# DDS_Sine_Sweeper.net
KiCad netlist of a schematic drawn in EAGLE
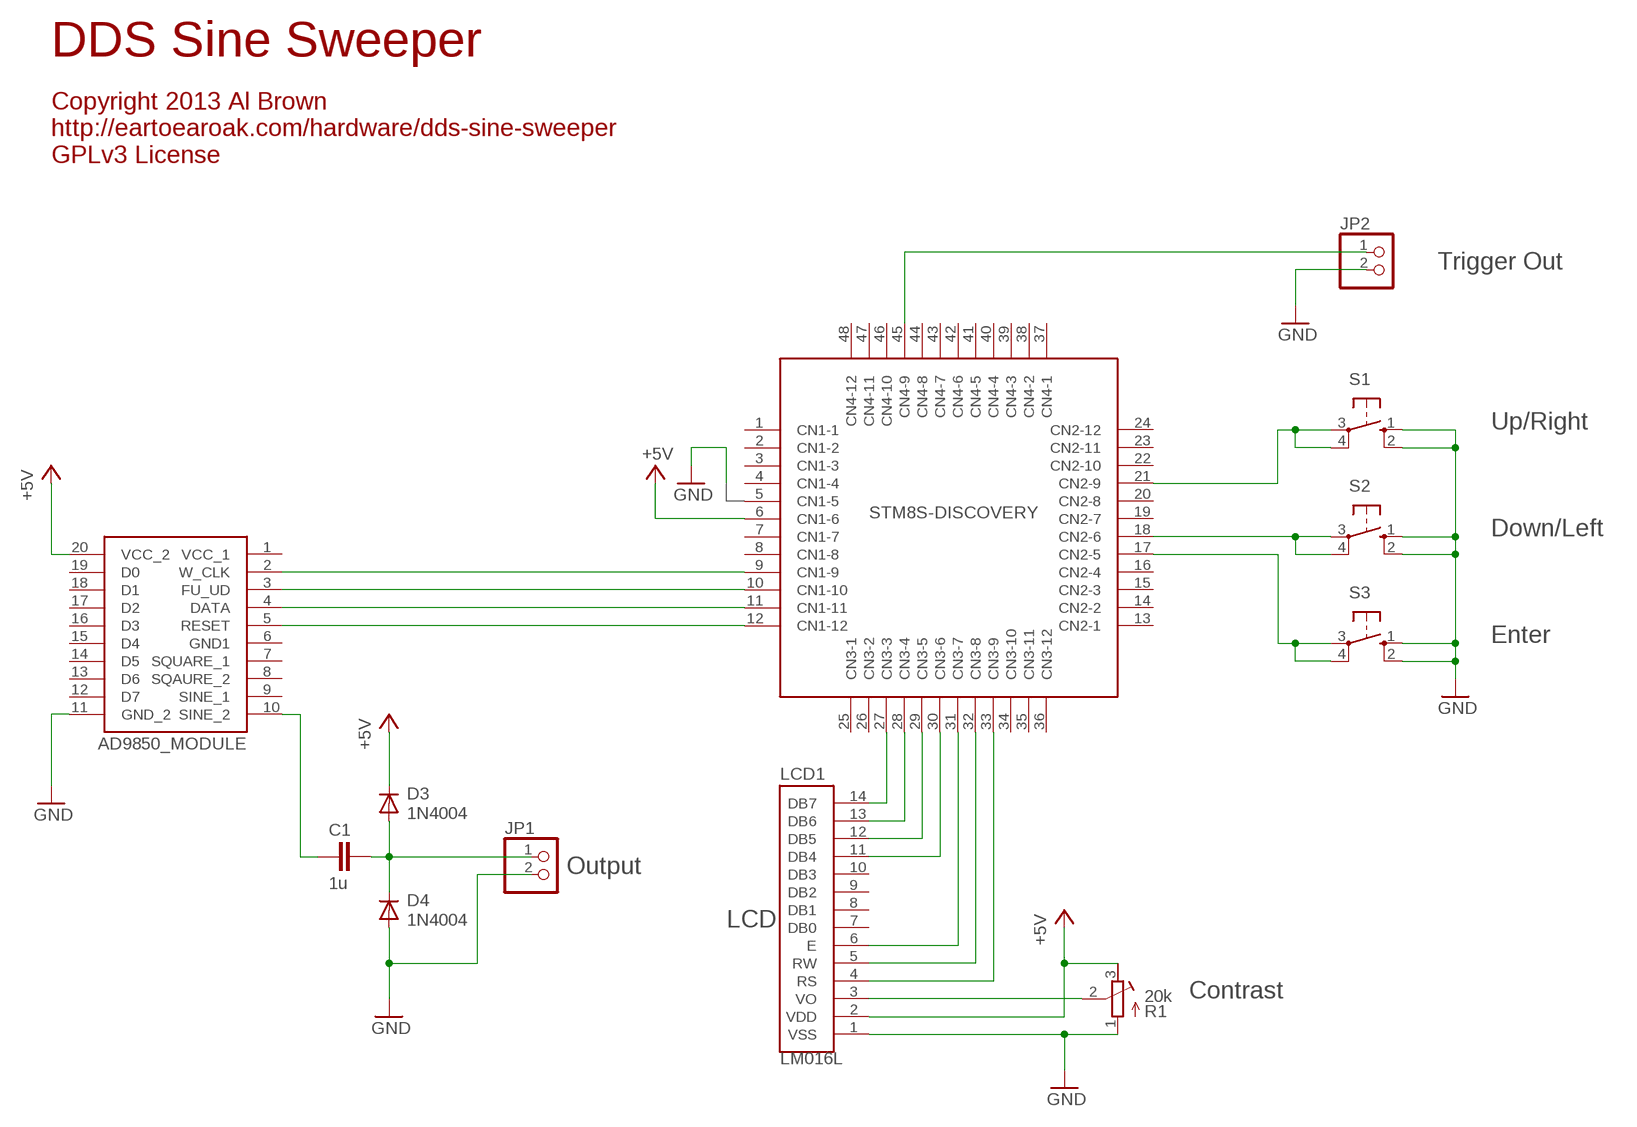
[diagram p0: schematic, sheet 1]

(export (version "E")
  (design (tool "Eeschema 10.0.6"))
  (components
    (comp (ref "BOARD1")
      (value "STM8S-DISCOVERY")
      (footprint "eagle-import:STM8S-DISCOVERY")
      (libsource (lib "eagle-import") (part "STM8S-DISCOVERY"))
    )
    (comp (ref "BOARD2")
      (value "AD9850_MODULE")
      (footprint "eagle-import:10X2")
      (libsource (lib "eagle-import") (part "AD9850_MODULE"))
    )
    (comp (ref "C1")
      (value "1u")
      (footprint "eagle-import:C025_050-024X070")
      (libsource (lib "eagle-import") (part "C-EUC025_050-024X070"))
    )
    (comp (ref "D3")
      (value "1N4004")
      (footprint "eagle-import:DO41-10")
      (libsource (lib "eagle-import") (part "1N4004"))
    )
    (comp (ref "D4")
      (value "1N4004")
      (footprint "eagle-import:DO41-10")
      (libsource (lib "eagle-import") (part "1N4004"))
    )
    (comp (ref "JP1")
      (value "PINHD-1X2")
      (footprint "eagle-import:1X02")
      (libsource (lib "eagle-import") (part "PINHD-1X2"))
    )
    (comp (ref "JP2")
      (value "PINHD-1X2")
      (footprint "eagle-import:1X02")
      (libsource (lib "eagle-import") (part "PINHD-1X2"))
    )
    (comp (ref "LCD1")
      (value "LM016L")
      (footprint "eagle-import:LM016L")
      (libsource (lib "eagle-import") (part "LM016L"))
    )
    (comp (ref "R1")
      (value "20k")
      (footprint "eagle-import:RTRIM3339P")
      (libsource (lib "eagle-import") (part "R-TRIMM3339P"))
    )
    (comp (ref "S1")
      (value "10-XX")
      (footprint "eagle-import:B3F-10XX")
      (fields (field (name "MPN") "B3F-1000"))
      (libsource (lib "eagle-import") (part "10-XX"))
    )
    (comp (ref "S2")
      (value "10-XX")
      (footprint "eagle-import:B3F-10XX")
      (fields (field (name "MPN") "B3F-1000"))
      (libsource (lib "eagle-import") (part "10-XX"))
    )
    (comp (ref "S3")
      (value "10-XX")
      (footprint "eagle-import:B3F-10XX")
      (fields (field (name "MPN") "B3F-1000"))
      (libsource (lib "eagle-import") (part "10-XX"))
    )
  )
  (nets
    (net (code "1") (name "+5V") (class "Default")
      (node (ref "BOARD1") (pin "6") (pinfunction "CN1-6_6") (pintype "bidirectional"))
      (node (ref "BOARD2") (pin "20") (pinfunction "VCC_2_20") (pintype "bidirectional"))
      (node (ref "D3") (pin "C") (pinfunction "C_C") (pintype "passive"))
      (node (ref "LCD1") (pin "2") (pinfunction "VDD_2") (pintype "bidirectional"))
      (node (ref "R1") (pin "3") (pinfunction "A_3") (pintype "passive"))
    )
    (net (code "2") (name "GND") (class "Default")
      (node (ref "BOARD2") (pin "11") (pinfunction "GND_2_11") (pintype "bidirectional"))
      (node (ref "D4") (pin "A") (pinfunction "A_A") (pintype "passive"))
      (node (ref "JP1") (pin "2") (pinfunction "2_2") (pintype "passive"))
      (node (ref "JP2") (pin "2") (pinfunction "2_2") (pintype "passive"))
      (node (ref "LCD1") (pin "1") (pinfunction "VSS_1") (pintype "bidirectional"))
      (node (ref "R1") (pin "1") (pinfunction "E_1") (pintype "passive"))
      (node (ref "S1") (pin "1") (pinfunction "S_1") (pintype "passive"))
      (node (ref "S1") (pin "2") (pinfunction "S1_2") (pintype "passive"))
      (node (ref "S2") (pin "1") (pinfunction "S_1") (pintype "passive"))
      (node (ref "S2") (pin "2") (pinfunction "S1_2") (pintype "passive"))
      (node (ref "S3") (pin "1") (pinfunction "S_1") (pintype "passive"))
      (node (ref "S3") (pin "2") (pinfunction "S1_2") (pintype "passive"))
    )
    (net (code "3") (name "Net-(BOARD1-CN1-9)") (class "Default")
      (node (ref "BOARD1") (pin "9") (pinfunction "CN1-9_9") (pintype "bidirectional"))
      (node (ref "BOARD2") (pin "2") (pinfunction "W_CLK_2") (pintype "bidirectional"))
    )
    (net (code "4") (name "Net-(BOARD1-CN1-10)") (class "Default")
      (node (ref "BOARD1") (pin "10") (pinfunction "CN1-10_10") (pintype "bidirectional"))
      (node (ref "BOARD2") (pin "3") (pinfunction "FU_UD_3") (pintype "bidirectional"))
    )
    (net (code "5") (name "Net-(BOARD1-CN1-11)") (class "Default")
      (node (ref "BOARD1") (pin "11") (pinfunction "CN1-11_11") (pintype "bidirectional"))
      (node (ref "BOARD2") (pin "4") (pinfunction "DATA_4") (pintype "bidirectional"))
    )
    (net (code "6") (name "Net-(BOARD1-CN1-12)") (class "Default")
      (node (ref "BOARD1") (pin "12") (pinfunction "CN1-12_12") (pintype "bidirectional"))
      (node (ref "BOARD2") (pin "5") (pinfunction "RESET_5") (pintype "bidirectional"))
    )
    (net (code "7") (name "Net-(BOARD1-CN2-5)") (class "Default")
      (node (ref "BOARD1") (pin "17") (pinfunction "CN2-5_17") (pintype "bidirectional"))
      (node (ref "S3") (pin "3") (pinfunction "P_3") (pintype "passive"))
      (node (ref "S3") (pin "4") (pinfunction "P1_4") (pintype "passive"))
    )
    (net (code "8") (name "Net-(BOARD1-CN2-6)") (class "Default")
      (node (ref "BOARD1") (pin "18") (pinfunction "CN2-6_18") (pintype "bidirectional"))
      (node (ref "S2") (pin "3") (pinfunction "P_3") (pintype "passive"))
      (node (ref "S2") (pin "4") (pinfunction "P1_4") (pintype "passive"))
    )
    (net (code "9") (name "Net-(BOARD1-CN2-9)") (class "Default")
      (node (ref "BOARD1") (pin "21") (pinfunction "CN2-9_21") (pintype "bidirectional"))
      (node (ref "S1") (pin "3") (pinfunction "P_3") (pintype "passive"))
      (node (ref "S1") (pin "4") (pinfunction "P1_4") (pintype "passive"))
    )
    (net (code "10") (name "Net-(BOARD1-CN3-3)") (class "Default")
      (node (ref "BOARD1") (pin "27") (pinfunction "CN3-3_27") (pintype "bidirectional"))
      (node (ref "LCD1") (pin "14") (pinfunction "DB7_14") (pintype "bidirectional"))
    )
    (net (code "11") (name "Net-(BOARD1-CN3-4)") (class "Default")
      (node (ref "BOARD1") (pin "28") (pinfunction "CN3-4_28") (pintype "bidirectional"))
      (node (ref "LCD1") (pin "13") (pinfunction "DB6_13") (pintype "bidirectional"))
    )
    (net (code "12") (name "Net-(BOARD1-CN3-5)") (class "Default")
      (node (ref "BOARD1") (pin "29") (pinfunction "CN3-5_29") (pintype "bidirectional"))
      (node (ref "LCD1") (pin "12") (pinfunction "DB5_12") (pintype "bidirectional"))
    )
    (net (code "13") (name "Net-(BOARD1-CN3-6)") (class "Default")
      (node (ref "BOARD1") (pin "30") (pinfunction "CN3-6_30") (pintype "bidirectional"))
      (node (ref "LCD1") (pin "11") (pinfunction "DB4_11") (pintype "bidirectional"))
    )
    (net (code "14") (name "Net-(BOARD1-CN3-7)") (class "Default")
      (node (ref "BOARD1") (pin "31") (pinfunction "CN3-7_31") (pintype "bidirectional"))
      (node (ref "LCD1") (pin "6") (pinfunction "E_6") (pintype "bidirectional"))
    )
    (net (code "15") (name "Net-(BOARD1-CN3-8)") (class "Default")
      (node (ref "BOARD1") (pin "32") (pinfunction "CN3-8_32") (pintype "bidirectional"))
      (node (ref "LCD1") (pin "5") (pinfunction "RW_5") (pintype "bidirectional"))
    )
    (net (code "16") (name "Net-(BOARD1-CN3-9)") (class "Default")
      (node (ref "BOARD1") (pin "33") (pinfunction "CN3-9_33") (pintype "bidirectional"))
      (node (ref "LCD1") (pin "4") (pinfunction "RS_4") (pintype "bidirectional"))
    )
    (net (code "17") (name "Net-(BOARD1-CN4-9)") (class "Default")
      (node (ref "BOARD1") (pin "45") (pinfunction "CN4-9_45") (pintype "bidirectional"))
      (node (ref "JP2") (pin "1") (pinfunction "1_1") (pintype "passive"))
    )
    (net (code "18") (name "Net-(BOARD2-SINE_2)") (class "Default")
      (node (ref "BOARD2") (pin "10") (pinfunction "SINE_2_10") (pintype "bidirectional"))
      (node (ref "C1") (pin "1") (pinfunction "1_1") (pintype "passive"))
    )
    (net (code "19") (name "Net-(C1-Pad2)") (class "Default")
      (node (ref "C1") (pin "2") (pinfunction "2_2") (pintype "passive"))
      (node (ref "D3") (pin "A") (pinfunction "A_A") (pintype "passive"))
      (node (ref "D4") (pin "C") (pinfunction "C_C") (pintype "passive"))
      (node (ref "JP1") (pin "1") (pinfunction "1_1") (pintype "passive"))
    )
    (net (code "20") (name "Net-(LCD1-VO)") (class "Default")
      (node (ref "LCD1") (pin "3") (pinfunction "VO_3") (pintype "bidirectional"))
      (node (ref "R1") (pin "2") (pinfunction "S_2") (pintype "passive"))
    )
    (net (code "21") (name "unconnected-(BOARD1-CN1-1-Pad1)") (class "Default")
      (node (ref "BOARD1") (pin "1") (pinfunction "CN1-1_1") (pintype "bidirectional"))
    )
    (net (code "22") (name "unconnected-(BOARD1-CN1-2-Pad2)") (class "Default")
      (node (ref "BOARD1") (pin "2") (pinfunction "CN1-2_2") (pintype "bidirectional"))
    )
    (net (code "23") (name "unconnected-(BOARD1-CN1-3-Pad3)") (class "Default")
      (node (ref "BOARD1") (pin "3") (pinfunction "CN1-3_3") (pintype "bidirectional"))
    )
    (net (code "24") (name "unconnected-(BOARD1-CN1-4-Pad4)") (class "Default")
      (node (ref "BOARD1") (pin "4") (pinfunction "CN1-4_4") (pintype "bidirectional"))
    )
    (net (code "25") (name "unconnected-(BOARD1-CN1-5-Pad5)") (class "Default")
      (node (ref "BOARD1") (pin "5") (pinfunction "CN1-5_5") (pintype "bidirectional"))
    )
    (net (code "26") (name "unconnected-(BOARD1-CN1-7-Pad7)") (class "Default")
      (node (ref "BOARD1") (pin "7") (pinfunction "CN1-7_7") (pintype "bidirectional"))
    )
    (net (code "27") (name "unconnected-(BOARD1-CN1-8-Pad8)") (class "Default")
      (node (ref "BOARD1") (pin "8") (pinfunction "CN1-8_8") (pintype "bidirectional"))
    )
    (net (code "28") (name "unconnected-(BOARD1-CN2-1-Pad13)") (class "Default")
      (node (ref "BOARD1") (pin "13") (pinfunction "CN2-1_13") (pintype "bidirectional"))
    )
    (net (code "29") (name "unconnected-(BOARD1-CN2-2-Pad14)") (class "Default")
      (node (ref "BOARD1") (pin "14") (pinfunction "CN2-2_14") (pintype "bidirectional"))
    )
    (net (code "30") (name "unconnected-(BOARD1-CN2-3-Pad15)") (class "Default")
      (node (ref "BOARD1") (pin "15") (pinfunction "CN2-3_15") (pintype "bidirectional"))
    )
    (net (code "31") (name "unconnected-(BOARD1-CN2-4-Pad16)") (class "Default")
      (node (ref "BOARD1") (pin "16") (pinfunction "CN2-4_16") (pintype "bidirectional"))
    )
    (net (code "32") (name "unconnected-(BOARD1-CN2-7-Pad19)") (class "Default")
      (node (ref "BOARD1") (pin "19") (pinfunction "CN2-7_19") (pintype "bidirectional"))
    )
    (net (code "33") (name "unconnected-(BOARD1-CN2-8-Pad20)") (class "Default")
      (node (ref "BOARD1") (pin "20") (pinfunction "CN2-8_20") (pintype "bidirectional"))
    )
    (net (code "34") (name "unconnected-(BOARD1-CN2-10-Pad22)") (class "Default")
      (node (ref "BOARD1") (pin "22") (pinfunction "CN2-10_22") (pintype "bidirectional"))
    )
    (net (code "35") (name "unconnected-(BOARD1-CN2-11-Pad23)") (class "Default")
      (node (ref "BOARD1") (pin "23") (pinfunction "CN2-11_23") (pintype "bidirectional"))
    )
    (net (code "36") (name "unconnected-(BOARD1-CN2-12-Pad24)") (class "Default")
      (node (ref "BOARD1") (pin "24") (pinfunction "CN2-12_24") (pintype "bidirectional"))
    )
    (net (code "37") (name "unconnected-(BOARD1-CN3-1-Pad25)") (class "Default")
      (node (ref "BOARD1") (pin "25") (pinfunction "CN3-1_25") (pintype "bidirectional"))
    )
    (net (code "38") (name "unconnected-(BOARD1-CN3-2-Pad26)") (class "Default")
      (node (ref "BOARD1") (pin "26") (pinfunction "CN3-2_26") (pintype "bidirectional"))
    )
    (net (code "39") (name "unconnected-(BOARD1-CN3-10-Pad34)") (class "Default")
      (node (ref "BOARD1") (pin "34") (pinfunction "CN3-10_34") (pintype "bidirectional"))
    )
    (net (code "40") (name "unconnected-(BOARD1-CN3-11-Pad35)") (class "Default")
      (node (ref "BOARD1") (pin "35") (pinfunction "CN3-11_35") (pintype "bidirectional"))
    )
    (net (code "41") (name "unconnected-(BOARD1-CN3-12-Pad36)") (class "Default")
      (node (ref "BOARD1") (pin "36") (pinfunction "CN3-12_36") (pintype "bidirectional"))
    )
    (net (code "42") (name "unconnected-(BOARD1-CN4-1-Pad37)") (class "Default")
      (node (ref "BOARD1") (pin "37") (pinfunction "CN4-1_37") (pintype "bidirectional"))
    )
    (net (code "43") (name "unconnected-(BOARD1-CN4-2-Pad38)") (class "Default")
      (node (ref "BOARD1") (pin "38") (pinfunction "CN4-2_38") (pintype "bidirectional"))
    )
    (net (code "44") (name "unconnected-(BOARD1-CN4-3-Pad39)") (class "Default")
      (node (ref "BOARD1") (pin "39") (pinfunction "CN4-3_39") (pintype "bidirectional"))
    )
    (net (code "45") (name "unconnected-(BOARD1-CN4-4-Pad40)") (class "Default")
      (node (ref "BOARD1") (pin "40") (pinfunction "CN4-4_40") (pintype "bidirectional"))
    )
    (net (code "46") (name "unconnected-(BOARD1-CN4-5-Pad41)") (class "Default")
      (node (ref "BOARD1") (pin "41") (pinfunction "CN4-5_41") (pintype "bidirectional"))
    )
    (net (code "47") (name "unconnected-(BOARD1-CN4-6-Pad42)") (class "Default")
      (node (ref "BOARD1") (pin "42") (pinfunction "CN4-6_42") (pintype "bidirectional"))
    )
    (net (code "48") (name "unconnected-(BOARD1-CN4-7-Pad43)") (class "Default")
      (node (ref "BOARD1") (pin "43") (pinfunction "CN4-7_43") (pintype "bidirectional"))
    )
    (net (code "49") (name "unconnected-(BOARD1-CN4-8-Pad44)") (class "Default")
      (node (ref "BOARD1") (pin "44") (pinfunction "CN4-8_44") (pintype "bidirectional"))
    )
    (net (code "50") (name "unconnected-(BOARD1-CN4-10-Pad46)") (class "Default")
      (node (ref "BOARD1") (pin "46") (pinfunction "CN4-10_46") (pintype "bidirectional"))
    )
    (net (code "51") (name "unconnected-(BOARD1-CN4-11-Pad47)") (class "Default")
      (node (ref "BOARD1") (pin "47") (pinfunction "CN4-11_47") (pintype "bidirectional"))
    )
    (net (code "52") (name "unconnected-(BOARD1-CN4-12-Pad48)") (class "Default")
      (node (ref "BOARD1") (pin "48") (pinfunction "CN4-12_48") (pintype "bidirectional"))
    )
    (net (code "53") (name "unconnected-(BOARD2-D0-Pad19)") (class "Default")
      (node (ref "BOARD2") (pin "19") (pinfunction "D0_19") (pintype "bidirectional"))
    )
    (net (code "54") (name "unconnected-(BOARD2-D1-Pad18)") (class "Default")
      (node (ref "BOARD2") (pin "18") (pinfunction "D1_18") (pintype "bidirectional"))
    )
    (net (code "55") (name "unconnected-(BOARD2-D2-Pad17)") (class "Default")
      (node (ref "BOARD2") (pin "17") (pinfunction "D2_17") (pintype "bidirectional"))
    )
    (net (code "56") (name "unconnected-(BOARD2-D3-Pad16)") (class "Default")
      (node (ref "BOARD2") (pin "16") (pinfunction "D3_16") (pintype "bidirectional"))
    )
    (net (code "57") (name "unconnected-(BOARD2-D4-Pad15)") (class "Default")
      (node (ref "BOARD2") (pin "15") (pinfunction "D4_15") (pintype "bidirectional"))
    )
    (net (code "58") (name "unconnected-(BOARD2-D5-Pad14)") (class "Default")
      (node (ref "BOARD2") (pin "14") (pinfunction "D5_14") (pintype "bidirectional"))
    )
    (net (code "59") (name "unconnected-(BOARD2-D6-Pad13)") (class "Default")
      (node (ref "BOARD2") (pin "13") (pinfunction "D6_13") (pintype "bidirectional"))
    )
    (net (code "60") (name "unconnected-(BOARD2-D7-Pad12)") (class "Default")
      (node (ref "BOARD2") (pin "12") (pinfunction "D7_12") (pintype "bidirectional"))
    )
    (net (code "61") (name "unconnected-(BOARD2-GND1-Pad6)") (class "Default")
      (node (ref "BOARD2") (pin "6") (pinfunction "GND1_6") (pintype "bidirectional"))
    )
    (net (code "62") (name "unconnected-(BOARD2-SINE_1-Pad9)") (class "Default")
      (node (ref "BOARD2") (pin "9") (pinfunction "SINE_1_9") (pintype "bidirectional"))
    )
    (net (code "63") (name "unconnected-(BOARD2-SQAURE_2-Pad8)") (class "Default")
      (node (ref "BOARD2") (pin "8") (pinfunction "SQAURE_2_8") (pintype "bidirectional"))
    )
    (net (code "64") (name "unconnected-(BOARD2-SQUARE_1-Pad7)") (class "Default")
      (node (ref "BOARD2") (pin "7") (pinfunction "SQUARE_1_7") (pintype "bidirectional"))
    )
    (net (code "65") (name "unconnected-(BOARD2-VCC_1-Pad1)") (class "Default")
      (node (ref "BOARD2") (pin "1") (pinfunction "VCC_1_1") (pintype "bidirectional"))
    )
    (net (code "66") (name "unconnected-(LCD1-DB0-Pad7)") (class "Default")
      (node (ref "LCD1") (pin "7") (pinfunction "DB0_7") (pintype "bidirectional"))
    )
    (net (code "67") (name "unconnected-(LCD1-DB1-Pad8)") (class "Default")
      (node (ref "LCD1") (pin "8") (pinfunction "DB1_8") (pintype "bidirectional"))
    )
    (net (code "68") (name "unconnected-(LCD1-DB2-Pad9)") (class "Default")
      (node (ref "LCD1") (pin "9") (pinfunction "DB2_9") (pintype "bidirectional"))
    )
    (net (code "69") (name "unconnected-(LCD1-DB3-Pad10)") (class "Default")
      (node (ref "LCD1") (pin "10") (pinfunction "DB3_10") (pintype "bidirectional"))
    )
  )
)
